# user.net
KiCad netlist of a schematic drawn in Altium Designer
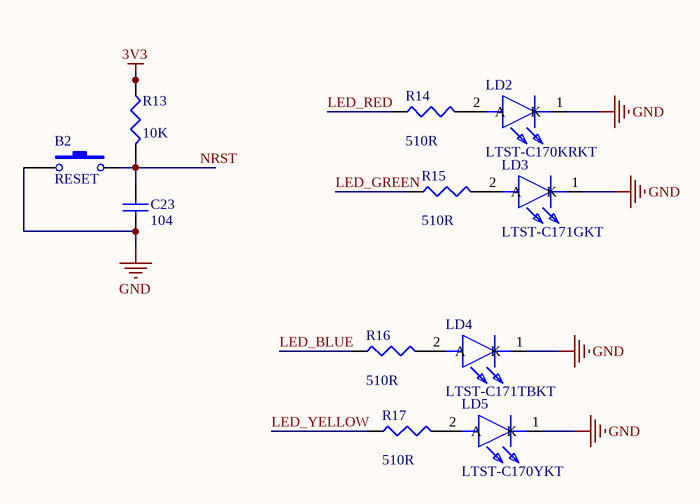
[diagram p0: user.SchDoc]

(export (version "E")
  (design (tool "Eeschema 10.0.6"))
  (components
    (comp (ref "B2")
      (value "RESET")
      (footprint "stm_copter:3-1825910-5")
      (description "Switch")
      (fields (field (name "PUBLISHER") "Altium Limited"))
      (libsource (lib "Miscellaneous Devices") (part "SW-PB"))
    )
    (comp (ref "C23")
      (value "104")
      (footprint "stm_copter:CAPC2012X98N")
      (description "Capacitor (Semiconductor SIM Model)")
      (fields (field (name "PUBLISHER") "Altium Limited"))
      (libsource (lib "syhaunguyen") (part "Cap Semi"))
    )
    (comp (ref "LD2")
      (value "LTST-C170KRKT")
      (footprint "stm_copter:LEDC2012X120N")
      (description "LED")
      (fields
        (field (name "MANUFACTURER_PART_NUMBER") "LTST-C171GKT")
        (field (name "MOUSER PART NUMBER") "859-LTST-C171GKT")
      )
      (libsource (lib "DRV8323_Lib") (part "LTST-C171GKT"))
    )
    (comp (ref "LD3")
      (value "LTST-C171GKT")
      (footprint "stm_copter:LEDC2012X90N")
      (description "LED")
      (fields
        (field (name "MOUSER PART NUMBER") "859-LTST-C171GKT")
        (field (name "RS PART NUMBER") "6920935P")
      )
      (libsource (lib "DRV8323_Lib") (part "LTST-C171GKT"))
    )
    (comp (ref "LD4")
      (value "LTST-C171TBKT")
      (footprint "stm_copter:LEDC2012X90N")
      (description "LED")
      (fields
        (field (name "MANUFACTURER_PART_NUMBER") "LTST-C171GKT")
        (field (name "MOUSER PART NUMBER") "859-LTST-C171GKT")
      )
      (libsource (lib "DRV8323_Lib") (part "LTST-C171GKT"))
    )
    (comp (ref "LD5")
      (value "LTST-C170YKT")
      (footprint "stm_copter:LEDC2012X120N")
      (description "LED")
      (fields
        (field (name "MANUFACTURER_PART_NUMBER") "LTST-C171GKT")
        (field (name "MOUSER PART NUMBER") "859-LTST-C171GKT")
      )
      (libsource (lib "DRV8323_Lib") (part "LTST-C171GKT"))
    )
    (comp (ref "R13")
      (value "10K")
      (footprint "stm_copter:RESC2012X60N")
      (description "Resistor")
      (fields (field (name "PUBLISHER") "Altium Limited"))
      (libsource (lib "Miscellaneous Devices") (part "Res3"))
    )
    (comp (ref "R14")
      (value "510R")
      (footprint "stm_copter:RESC1608X55N")
      (description "Resistor")
      (fields (field (name "PUBLISHER") "Altium Limited"))
      (libsource (lib "Miscellaneous Devices") (part "Res3"))
    )
    (comp (ref "R15")
      (value "510R")
      (footprint "stm_copter:RESC1608X55N")
      (description "Resistor")
      (fields (field (name "PUBLISHER") "Altium Limited"))
      (libsource (lib "Miscellaneous Devices") (part "Res3"))
    )
    (comp (ref "R16")
      (value "510R")
      (footprint "stm_copter:RESC1608X55N")
      (description "Resistor")
      (fields (field (name "PUBLISHER") "Altium Limited"))
      (libsource (lib "Miscellaneous Devices") (part "Res3"))
    )
    (comp (ref "R17")
      (value "510R")
      (footprint "stm_copter:RESC1608X55N")
      (description "Resistor")
      (fields (field (name "PUBLISHER") "Altium Limited"))
      (libsource (lib "Miscellaneous Devices") (part "Res3"))
    )
  )
  (nets
    (net (code "1") (name "/LED_BLUE") (class "Default")
      (node (ref "R16") (pin "1") (pinfunction "1_1") (pintype "passive"))
    )
    (net (code "2") (name "/LED_GREEN") (class "Default")
      (node (ref "R15") (pin "1") (pinfunction "1_1") (pintype "passive"))
    )
    (net (code "3") (name "/LED_RED") (class "Default")
      (node (ref "R14") (pin "1") (pinfunction "1_1") (pintype "passive"))
    )
    (net (code "4") (name "/LED_YELLOW") (class "Default")
      (node (ref "R17") (pin "1") (pinfunction "1_1") (pintype "passive"))
    )
    (net (code "5") (name "/NRST") (class "Default")
      (node (ref "B2") (pin "2") (pinfunction "2_2") (pintype "passive"))
      (node (ref "C23") (pin "1") (pinfunction "1_1") (pintype "passive"))
      (node (ref "R13") (pin "2") (pinfunction "2_2") (pintype "passive"))
    )
    (net (code "6") (name "3V3") (class "Default")
      (node (ref "R13") (pin "1") (pinfunction "1_1") (pintype "passive"))
    )
    (net (code "7") (name "GND") (class "Default")
      (node (ref "B2") (pin "1") (pinfunction "1_1") (pintype "passive"))
      (node (ref "C23") (pin "2") (pinfunction "2_2") (pintype "passive"))
      (node (ref "LD2") (pin "1") (pinfunction "K_1") (pintype "passive"))
      (node (ref "LD3") (pin "1") (pinfunction "K_1") (pintype "passive"))
      (node (ref "LD4") (pin "1") (pinfunction "K_1") (pintype "passive"))
      (node (ref "LD5") (pin "1") (pinfunction "K_1") (pintype "passive"))
    )
    (net (code "8") (name "Net-(LD2-A)") (class "Default")
      (node (ref "LD2") (pin "2") (pinfunction "A_2") (pintype "passive"))
      (node (ref "R14") (pin "2") (pinfunction "2_2") (pintype "passive"))
    )
    (net (code "9") (name "Net-(LD3-A)") (class "Default")
      (node (ref "LD3") (pin "2") (pinfunction "A_2") (pintype "passive"))
      (node (ref "R15") (pin "2") (pinfunction "2_2") (pintype "passive"))
    )
    (net (code "10") (name "Net-(LD4-A)") (class "Default")
      (node (ref "LD4") (pin "2") (pinfunction "A_2") (pintype "passive"))
      (node (ref "R16") (pin "2") (pinfunction "2_2") (pintype "passive"))
    )
    (net (code "11") (name "Net-(LD5-A)") (class "Default")
      (node (ref "LD5") (pin "2") (pinfunction "A_2") (pintype "passive"))
      (node (ref "R17") (pin "2") (pinfunction "2_2") (pintype "passive"))
    )
  )
)
